# Xor_Not.net
KiCad netlist of a schematic drawn in EAGLE
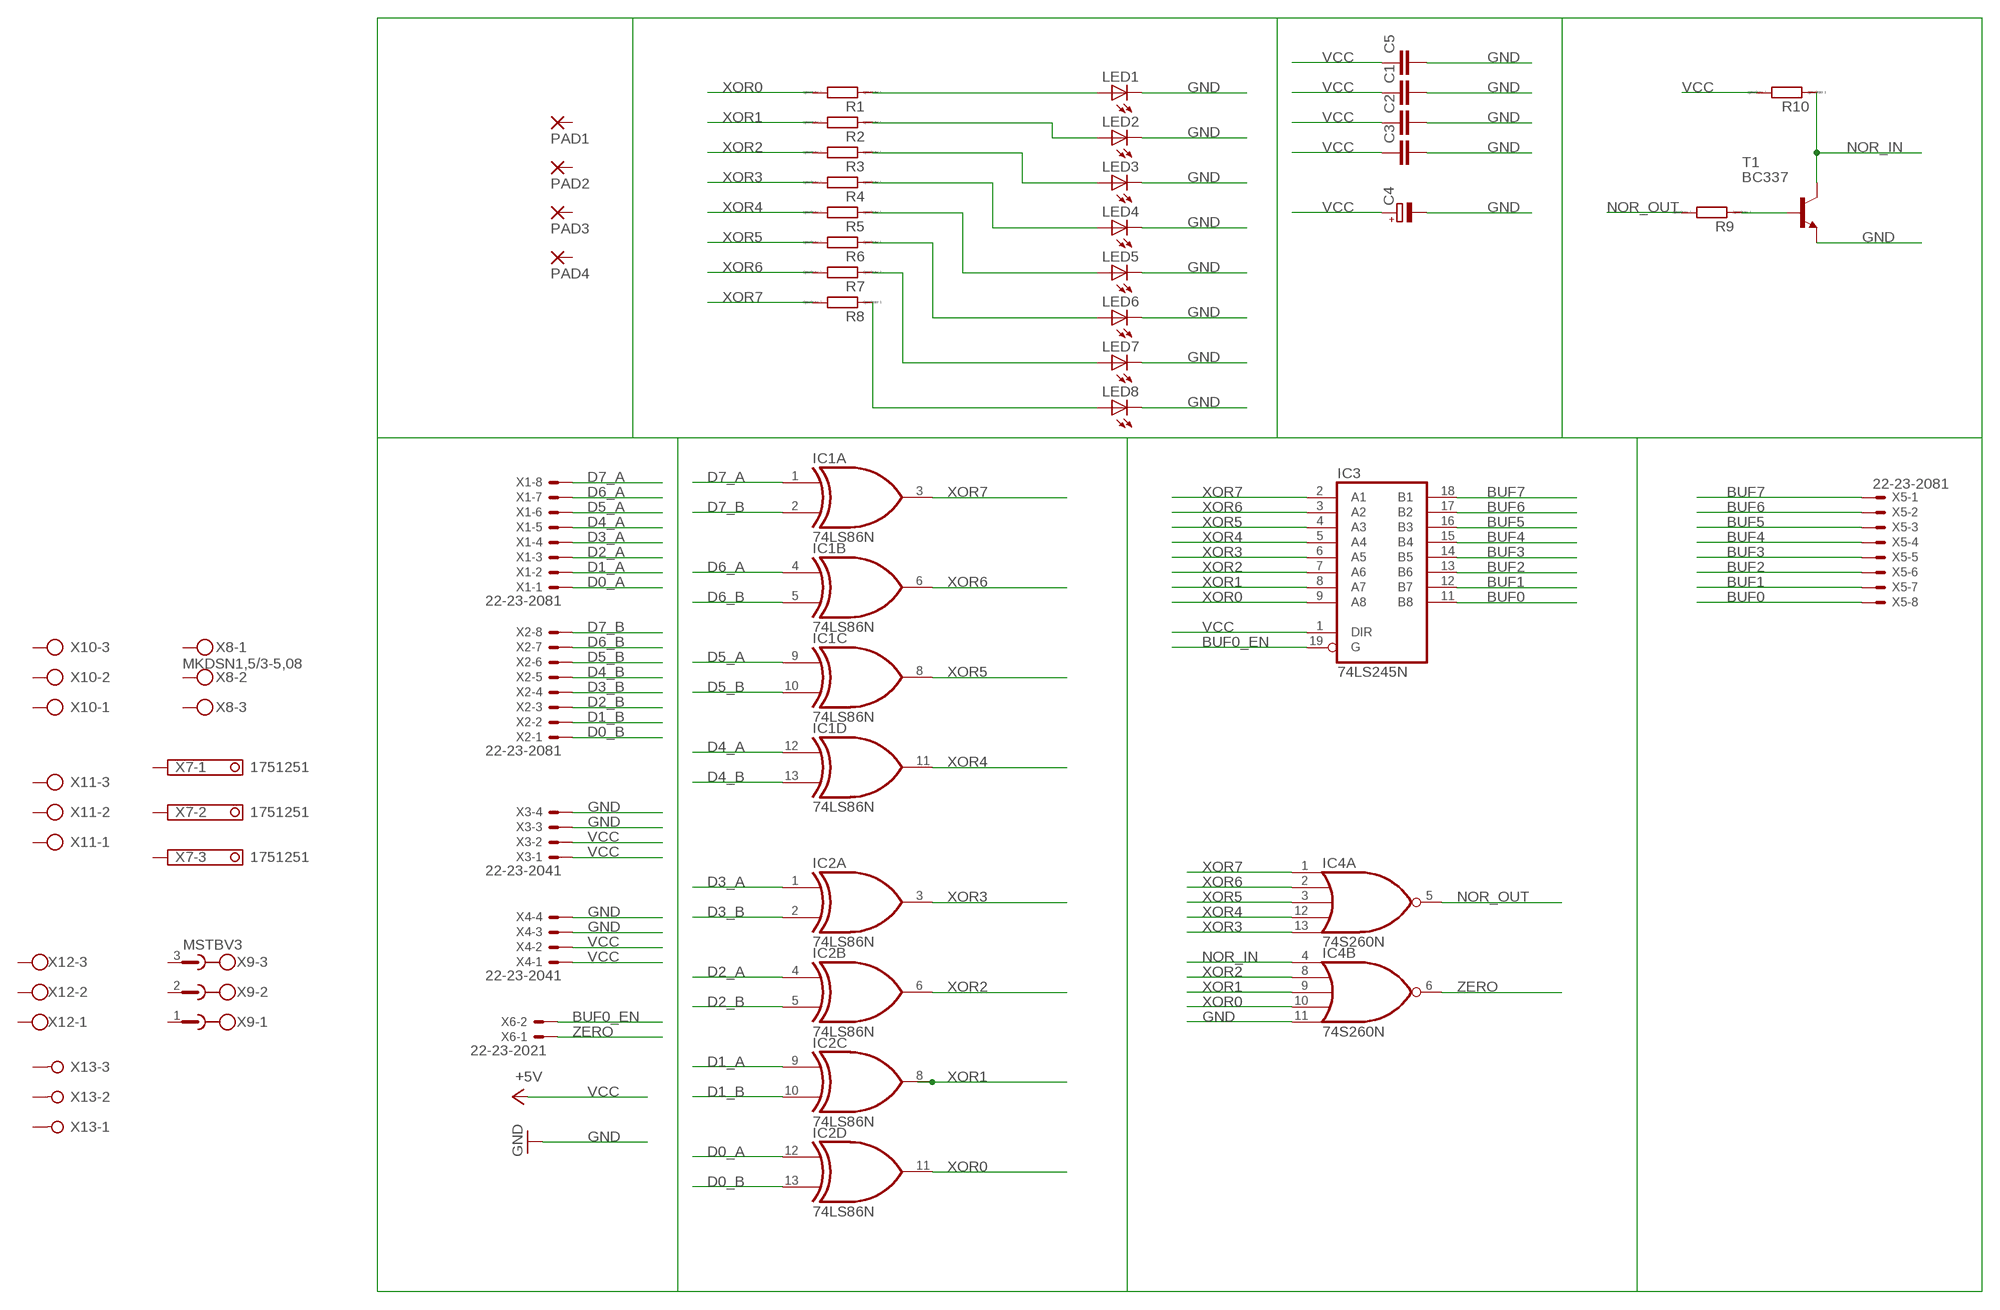
[diagram p0: schematic, sheet 1]

(export (version "E")
  (design (tool "Eeschema 10.0.6"))
  (components
    (comp (ref "C1")
      (value "C-EU025-025X050")
      (footprint "eagle-import:C025-025X050")
      (libsource (lib "eagle-import") (part "C-EU025-025X050"))
    )
    (comp (ref "C2")
      (value "C-EU025-025X050")
      (footprint "eagle-import:C025-025X050")
      (libsource (lib "eagle-import") (part "C-EU025-025X050"))
    )
    (comp (ref "C3")
      (value "C-EU025-025X050")
      (footprint "eagle-import:C025-025X050")
      (libsource (lib "eagle-import") (part "C-EU025-025X050"))
    )
    (comp (ref "C4")
      (value "CPOL-EUE2.5-6")
      (footprint "eagle-import:E2,5-6")
      (libsource (lib "eagle-import") (part "CPOL-EUE2.5-6"))
    )
    (comp (ref "C5")
      (value "C-EU025-025X050")
      (footprint "eagle-import:C025-025X050")
      (libsource (lib "eagle-import") (part "C-EU025-025X050"))
    )
    (comp (ref "IC1")
      (value "74LS86N")
      (footprint "eagle-import:DIL14")
      (libsource (lib "eagle-import") (part "7486NLS"))
    )
    (comp (ref "IC2")
      (value "74LS86N")
      (footprint "eagle-import:DIL14")
      (libsource (lib "eagle-import") (part "7486NLS"))
    )
    (comp (ref "IC3")
      (value "74LS245N")
      (footprint "eagle-import:DIL20")
      (libsource (lib "eagle-import") (part "74245NLS"))
    )
    (comp (ref "IC4")
      (value "74S260N")
      (footprint "eagle-import:DIL14")
      (libsource (lib "eagle-import") (part "74260NS"))
    )
    (comp (ref "LED1")
      (value "LED5MM")
      (footprint "eagle-import:LED5MM")
      (libsource (lib "eagle-import") (part "LED5MM"))
    )
    (comp (ref "LED2")
      (value "LED5MM")
      (footprint "eagle-import:LED5MM")
      (libsource (lib "eagle-import") (part "LED5MM"))
    )
    (comp (ref "LED3")
      (value "LED5MM")
      (footprint "eagle-import:LED5MM")
      (libsource (lib "eagle-import") (part "LED5MM"))
    )
    (comp (ref "LED4")
      (value "LED5MM")
      (footprint "eagle-import:LED5MM")
      (libsource (lib "eagle-import") (part "LED5MM"))
    )
    (comp (ref "LED5")
      (value "LED5MM")
      (footprint "eagle-import:LED5MM")
      (libsource (lib "eagle-import") (part "LED5MM"))
    )
    (comp (ref "LED6")
      (value "LED5MM")
      (footprint "eagle-import:LED5MM")
      (libsource (lib "eagle-import") (part "LED5MM"))
    )
    (comp (ref "LED7")
      (value "LED5MM")
      (footprint "eagle-import:LED5MM")
      (libsource (lib "eagle-import") (part "LED5MM"))
    )
    (comp (ref "LED8")
      (value "LED5MM")
      (footprint "eagle-import:LED5MM")
      (libsource (lib "eagle-import") (part "LED5MM"))
    )
    (comp (ref "PAD1")
      (value "3,17/1,3")
      (footprint "eagle-import:3,17_1,3")
      (libsource (lib "eagle-import") (part "3,17/1,3"))
    )
    (comp (ref "PAD2")
      (value "3,17/1,3")
      (footprint "eagle-import:3,17_1,3")
      (libsource (lib "eagle-import") (part "3,17/1,3"))
    )
    (comp (ref "PAD3")
      (value "3,17/1,3")
      (footprint "eagle-import:3,17_1,3")
      (libsource (lib "eagle-import") (part "3,17/1,3"))
    )
    (comp (ref "PAD4")
      (value "3,17/1,3")
      (footprint "eagle-import:3,17_1,3")
      (libsource (lib "eagle-import") (part "3,17/1,3"))
    )
    (comp (ref "R1")
      (value "R0207/10")
      (footprint "eagle-import:0207_10")
      (libsource (lib "eagle-import") (part "R0207/10"))
    )
    (comp (ref "R2")
      (value "R0207/10")
      (footprint "eagle-import:0207_10")
      (libsource (lib "eagle-import") (part "R0207/10"))
    )
    (comp (ref "R3")
      (value "R0207/10")
      (footprint "eagle-import:0207_10")
      (libsource (lib "eagle-import") (part "R0207/10"))
    )
    (comp (ref "R4")
      (value "R0207/10")
      (footprint "eagle-import:0207_10")
      (libsource (lib "eagle-import") (part "R0207/10"))
    )
    (comp (ref "R5")
      (value "R0207/10")
      (footprint "eagle-import:0207_10")
      (libsource (lib "eagle-import") (part "R0207/10"))
    )
    (comp (ref "R6")
      (value "R0207/10")
      (footprint "eagle-import:0207_10")
      (libsource (lib "eagle-import") (part "R0207/10"))
    )
    (comp (ref "R7")
      (value "R0207/10")
      (footprint "eagle-import:0207_10")
      (libsource (lib "eagle-import") (part "R0207/10"))
    )
    (comp (ref "R8")
      (value "R0207/10")
      (footprint "eagle-import:0207_10")
      (libsource (lib "eagle-import") (part "R0207/10"))
    )
    (comp (ref "R9")
      (value "R0207/10")
      (footprint "eagle-import:0207_10")
      (libsource (lib "eagle-import") (part "R0207/10"))
    )
    (comp (ref "R10")
      (value "R0207/10")
      (footprint "eagle-import:0207_10")
      (libsource (lib "eagle-import") (part "R0207/10"))
    )
    (comp (ref "T1")
      (value "BC337")
      (footprint "eagle-import:TO92")
      (libsource (lib "eagle-import") (part "BC337"))
    )
    (comp (ref "X1")
      (value "22-23-2081")
      (footprint "eagle-import:22-23-2081")
      (fields (field (name "MF") "MOLEX"))
      (libsource (lib "eagle-import") (part "22-23-2081"))
    )
    (comp (ref "X2")
      (value "22-23-2081")
      (footprint "eagle-import:22-23-2081")
      (fields (field (name "MF") "MOLEX"))
      (libsource (lib "eagle-import") (part "22-23-2081"))
    )
    (comp (ref "X3")
      (value "22-23-2041")
      (footprint "eagle-import:22-23-2041")
      (fields (field (name "MF") "MOLEX"))
      (libsource (lib "eagle-import") (part "22-23-2041"))
    )
    (comp (ref "X4")
      (value "22-23-2041")
      (footprint "eagle-import:22-23-2041")
      (fields (field (name "MF") "MOLEX"))
      (libsource (lib "eagle-import") (part "22-23-2041"))
    )
    (comp (ref "X5")
      (value "22-23-2081")
      (footprint "eagle-import:22-23-2081")
      (fields (field (name "MF") "MOLEX"))
      (libsource (lib "eagle-import") (part "22-23-2081"))
    )
    (comp (ref "X6")
      (value "22-23-2021")
      (footprint "eagle-import:22-23-2021")
      (fields (field (name "MF") "MOLEX"))
      (libsource (lib "eagle-import") (part "22-23-2021"))
    )
    (comp (ref "X7")
      (value "1751251")
      (footprint "eagle-import:1751251")
      (libsource (lib "eagle-import") (part "1751251"))
    )
    (comp (ref "X8")
      (value "MKDSN1,5/3-5,08")
      (footprint "eagle-import:MKDSN1,5_3-5,08")
      (libsource (lib "eagle-import") (part "MKDSN1,5/3-5,08"))
    )
    (comp (ref "X9")
      (value "MSTBV3")
      (footprint "eagle-import:MSTBV3")
      (fields (field (name "MPN") "MSTBV 2,5/3-GF-5.08"))
      (libsource (lib "eagle-import") (part "MSTBV3"))
    )
    (comp (ref "X10")
      (value "AK300/3")
      (footprint "eagle-import:AK300_3")
      (libsource (lib "eagle-import") (part "AK300/3"))
    )
    (comp (ref "X11")
      (value "AK500/3-H")
      (footprint "eagle-import:AK500_3-H")
      (libsource (lib "eagle-import") (part "AK500/3-H"))
    )
    (comp (ref "X12")
      (value "W237-103")
      (footprint "eagle-import:W237-103")
      (fields (field (name "MPN") "237-103"))
      (libsource (lib "eagle-import") (part "W237-103"))
    )
    (comp (ref "X13")
      (value "W237-03P")
      (footprint "eagle-import:W237-133")
      (libsource (lib "eagle-import") (part "W237-03P"))
    )
  )
  (nets
    (net (code "1") (name "+5V") (class "Default")
      (node (ref "C1") (pin "1") (pinfunction "1_1") (pintype "passive"))
      (node (ref "C2") (pin "1") (pinfunction "1_1") (pintype "passive"))
      (node (ref "C3") (pin "1") (pinfunction "1_1") (pintype "passive"))
      (node (ref "C4") (pin "+") (pinfunction "+_+") (pintype "passive"))
      (node (ref "C5") (pin "1") (pinfunction "1_1") (pintype "passive"))
      (node (ref "IC3") (pin "1") (pinfunction "DIR_1") (pintype "input"))
      (node (ref "R10") (pin "2") (pinfunction "2_2") (pintype "passive"))
      (node (ref "X3") (pin "1") (pinfunction "S_1") (pintype "passive"))
      (node (ref "X3") (pin "2") (pinfunction "S_2") (pintype "passive"))
      (node (ref "X4") (pin "1") (pinfunction "S_1") (pintype "passive"))
      (node (ref "X4") (pin "2") (pinfunction "S_2") (pintype "passive"))
    )
    (net (code "2") (name "/BUF0") (class "Default")
      (node (ref "IC3") (pin "11") (pinfunction "B8_11") (pintype "bidirectional"))
      (node (ref "X5") (pin "8") (pinfunction "S_8") (pintype "passive"))
    )
    (net (code "3") (name "/BUF0_EN") (class "Default")
      (node (ref "IC3") (pin "19") (pinfunction "G_19") (pintype "input"))
      (node (ref "X6") (pin "2") (pinfunction "S_2") (pintype "passive"))
    )
    (net (code "4") (name "/BUF1") (class "Default")
      (node (ref "IC3") (pin "12") (pinfunction "B7_12") (pintype "bidirectional"))
      (node (ref "X5") (pin "7") (pinfunction "S_7") (pintype "passive"))
    )
    (net (code "5") (name "/BUF2") (class "Default")
      (node (ref "IC3") (pin "13") (pinfunction "B6_13") (pintype "bidirectional"))
      (node (ref "X5") (pin "6") (pinfunction "S_6") (pintype "passive"))
    )
    (net (code "6") (name "/BUF3") (class "Default")
      (node (ref "IC3") (pin "14") (pinfunction "B5_14") (pintype "bidirectional"))
      (node (ref "X5") (pin "5") (pinfunction "S_5") (pintype "passive"))
    )
    (net (code "7") (name "/BUF4") (class "Default")
      (node (ref "IC3") (pin "15") (pinfunction "B4_15") (pintype "bidirectional"))
      (node (ref "X5") (pin "4") (pinfunction "S_4") (pintype "passive"))
    )
    (net (code "8") (name "/BUF5") (class "Default")
      (node (ref "IC3") (pin "16") (pinfunction "B3_16") (pintype "bidirectional"))
      (node (ref "X5") (pin "3") (pinfunction "S_3") (pintype "passive"))
    )
    (net (code "9") (name "/BUF6") (class "Default")
      (node (ref "IC3") (pin "17") (pinfunction "B2_17") (pintype "bidirectional"))
      (node (ref "X5") (pin "2") (pinfunction "S_2") (pintype "passive"))
    )
    (net (code "10") (name "/BUF7") (class "Default")
      (node (ref "IC3") (pin "18") (pinfunction "B1_18") (pintype "bidirectional"))
      (node (ref "X5") (pin "1") (pinfunction "S_1") (pintype "passive"))
    )
    (net (code "11") (name "/D0_A") (class "Default")
      (node (ref "IC2") (pin "12") (pinfunction "I0_12") (pintype "input"))
      (node (ref "X1") (pin "1") (pinfunction "S_1") (pintype "passive"))
    )
    (net (code "12") (name "/D0_B") (class "Default")
      (node (ref "IC2") (pin "13") (pinfunction "I1_13") (pintype "input"))
      (node (ref "X2") (pin "1") (pinfunction "S_1") (pintype "passive"))
    )
    (net (code "13") (name "/D1_A") (class "Default")
      (node (ref "IC2") (pin "9") (pinfunction "I0_9") (pintype "input"))
      (node (ref "X1") (pin "2") (pinfunction "S_2") (pintype "passive"))
    )
    (net (code "14") (name "/D1_B") (class "Default")
      (node (ref "IC2") (pin "10") (pinfunction "I1_10") (pintype "input"))
      (node (ref "X2") (pin "2") (pinfunction "S_2") (pintype "passive"))
    )
    (net (code "15") (name "/D2_A") (class "Default")
      (node (ref "IC2") (pin "4") (pinfunction "I0_4") (pintype "input"))
      (node (ref "X1") (pin "3") (pinfunction "S_3") (pintype "passive"))
    )
    (net (code "16") (name "/D2_B") (class "Default")
      (node (ref "IC2") (pin "5") (pinfunction "I1_5") (pintype "input"))
      (node (ref "X2") (pin "3") (pinfunction "S_3") (pintype "passive"))
    )
    (net (code "17") (name "/D3_A") (class "Default")
      (node (ref "IC2") (pin "1") (pinfunction "I0_1") (pintype "input"))
      (node (ref "X1") (pin "4") (pinfunction "S_4") (pintype "passive"))
    )
    (net (code "18") (name "/D3_B") (class "Default")
      (node (ref "IC2") (pin "2") (pinfunction "I1_2") (pintype "input"))
      (node (ref "X2") (pin "4") (pinfunction "S_4") (pintype "passive"))
    )
    (net (code "19") (name "/D4_A") (class "Default")
      (node (ref "IC1") (pin "12") (pinfunction "I0_12") (pintype "input"))
      (node (ref "X1") (pin "5") (pinfunction "S_5") (pintype "passive"))
    )
    (net (code "20") (name "/D4_B") (class "Default")
      (node (ref "IC1") (pin "13") (pinfunction "I1_13") (pintype "input"))
      (node (ref "X2") (pin "5") (pinfunction "S_5") (pintype "passive"))
    )
    (net (code "21") (name "/D5_A") (class "Default")
      (node (ref "IC1") (pin "9") (pinfunction "I0_9") (pintype "input"))
      (node (ref "X1") (pin "6") (pinfunction "S_6") (pintype "passive"))
    )
    (net (code "22") (name "/D5_B") (class "Default")
      (node (ref "IC1") (pin "10") (pinfunction "I1_10") (pintype "input"))
      (node (ref "X2") (pin "6") (pinfunction "S_6") (pintype "passive"))
    )
    (net (code "23") (name "/D6_A") (class "Default")
      (node (ref "IC1") (pin "4") (pinfunction "I0_4") (pintype "input"))
      (node (ref "X1") (pin "7") (pinfunction "S_7") (pintype "passive"))
    )
    (net (code "24") (name "/D6_B") (class "Default")
      (node (ref "IC1") (pin "5") (pinfunction "I1_5") (pintype "input"))
      (node (ref "X2") (pin "7") (pinfunction "S_7") (pintype "passive"))
    )
    (net (code "25") (name "/D7_A") (class "Default")
      (node (ref "IC1") (pin "1") (pinfunction "I0_1") (pintype "input"))
      (node (ref "X1") (pin "8") (pinfunction "S_8") (pintype "passive"))
    )
    (net (code "26") (name "/D7_B") (class "Default")
      (node (ref "IC1") (pin "2") (pinfunction "I1_2") (pintype "input"))
      (node (ref "X2") (pin "8") (pinfunction "S_8") (pintype "passive"))
    )
    (net (code "27") (name "/NOR_IN") (class "Default")
      (node (ref "IC4") (pin "4") (pinfunction "I0_4") (pintype "input"))
      (node (ref "R10") (pin "1") (pinfunction "1_1") (pintype "passive"))
      (node (ref "T1") (pin "3") (pinfunction "C_3") (pintype "passive"))
    )
    (net (code "28") (name "/NOR_OUT") (class "Default")
      (node (ref "IC4") (pin "5") (pinfunction "O_5") (pintype "output"))
      (node (ref "R9") (pin "2") (pinfunction "2_2") (pintype "passive"))
    )
    (net (code "29") (name "/XOR0") (class "Default")
      (node (ref "IC2") (pin "11") (pinfunction "O_11") (pintype "output"))
      (node (ref "IC3") (pin "9") (pinfunction "A8_9") (pintype "bidirectional"))
      (node (ref "IC4") (pin "10") (pinfunction "I3_10") (pintype "input"))
      (node (ref "R1") (pin "2") (pinfunction "2_2") (pintype "passive"))
    )
    (net (code "30") (name "/XOR1") (class "Default")
      (node (ref "IC2") (pin "8") (pinfunction "O_8") (pintype "output"))
      (node (ref "IC3") (pin "8") (pinfunction "A7_8") (pintype "bidirectional"))
      (node (ref "IC4") (pin "9") (pinfunction "I2_9") (pintype "input"))
      (node (ref "R2") (pin "2") (pinfunction "2_2") (pintype "passive"))
    )
    (net (code "31") (name "/XOR2") (class "Default")
      (node (ref "IC2") (pin "6") (pinfunction "O_6") (pintype "output"))
      (node (ref "IC3") (pin "7") (pinfunction "A6_7") (pintype "bidirectional"))
      (node (ref "IC4") (pin "8") (pinfunction "I1_8") (pintype "input"))
      (node (ref "R3") (pin "2") (pinfunction "2_2") (pintype "passive"))
    )
    (net (code "32") (name "/XOR3") (class "Default")
      (node (ref "IC2") (pin "3") (pinfunction "O_3") (pintype "output"))
      (node (ref "IC3") (pin "6") (pinfunction "A5_6") (pintype "bidirectional"))
      (node (ref "IC4") (pin "13") (pinfunction "I4_13") (pintype "input"))
      (node (ref "R4") (pin "2") (pinfunction "2_2") (pintype "passive"))
    )
    (net (code "33") (name "/XOR4") (class "Default")
      (node (ref "IC1") (pin "11") (pinfunction "O_11") (pintype "output"))
      (node (ref "IC3") (pin "5") (pinfunction "A4_5") (pintype "bidirectional"))
      (node (ref "IC4") (pin "12") (pinfunction "I3_12") (pintype "input"))
      (node (ref "R5") (pin "2") (pinfunction "2_2") (pintype "passive"))
    )
    (net (code "34") (name "/XOR5") (class "Default")
      (node (ref "IC1") (pin "8") (pinfunction "O_8") (pintype "output"))
      (node (ref "IC3") (pin "4") (pinfunction "A3_4") (pintype "bidirectional"))
      (node (ref "IC4") (pin "3") (pinfunction "I2_3") (pintype "input"))
      (node (ref "R6") (pin "2") (pinfunction "2_2") (pintype "passive"))
    )
    (net (code "35") (name "/XOR6") (class "Default")
      (node (ref "IC1") (pin "6") (pinfunction "O_6") (pintype "output"))
      (node (ref "IC3") (pin "3") (pinfunction "A2_3") (pintype "bidirectional"))
      (node (ref "IC4") (pin "2") (pinfunction "I1_2") (pintype "input"))
      (node (ref "R7") (pin "2") (pinfunction "2_2") (pintype "passive"))
    )
    (net (code "36") (name "/XOR7") (class "Default")
      (node (ref "IC1") (pin "3") (pinfunction "O_3") (pintype "output"))
      (node (ref "IC3") (pin "2") (pinfunction "A1_2") (pintype "bidirectional"))
      (node (ref "IC4") (pin "1") (pinfunction "I0_1") (pintype "input"))
      (node (ref "R8") (pin "2") (pinfunction "2_2") (pintype "passive"))
    )
    (net (code "37") (name "/ZERO") (class "Default")
      (node (ref "IC4") (pin "6") (pinfunction "O_6") (pintype "output"))
      (node (ref "X6") (pin "1") (pinfunction "S_1") (pintype "passive"))
    )
    (net (code "38") (name "GND") (class "Default")
      (node (ref "C1") (pin "2") (pinfunction "2_2") (pintype "passive"))
      (node (ref "C2") (pin "2") (pinfunction "2_2") (pintype "passive"))
      (node (ref "C3") (pin "2") (pinfunction "2_2") (pintype "passive"))
      (node (ref "C4") (pin "-") (pinfunction "-_-") (pintype "passive"))
      (node (ref "C5") (pin "2") (pinfunction "2_2") (pintype "passive"))
      (node (ref "IC4") (pin "11") (pinfunction "I4_11") (pintype "input"))
      (node (ref "LED1") (pin "K") (pinfunction "C_K") (pintype "passive"))
      (node (ref "LED2") (pin "K") (pinfunction "C_K") (pintype "passive"))
      (node (ref "LED3") (pin "K") (pinfunction "C_K") (pintype "passive"))
      (node (ref "LED4") (pin "K") (pinfunction "C_K") (pintype "passive"))
      (node (ref "LED5") (pin "K") (pinfunction "C_K") (pintype "passive"))
      (node (ref "LED6") (pin "K") (pinfunction "C_K") (pintype "passive"))
      (node (ref "LED7") (pin "K") (pinfunction "C_K") (pintype "passive"))
      (node (ref "LED8") (pin "K") (pinfunction "C_K") (pintype "passive"))
      (node (ref "T1") (pin "1") (pinfunction "E_1") (pintype "passive"))
      (node (ref "X3") (pin "3") (pinfunction "S_3") (pintype "passive"))
      (node (ref "X3") (pin "4") (pinfunction "S_4") (pintype "passive"))
      (node (ref "X4") (pin "3") (pinfunction "S_3") (pintype "passive"))
      (node (ref "X4") (pin "4") (pinfunction "S_4") (pintype "passive"))
    )
    (net (code "39") (name "Net-(LED1-PadA)") (class "Default")
      (node (ref "LED1") (pin "A") (pinfunction "A_A") (pintype "passive"))
      (node (ref "R1") (pin "1") (pinfunction "1_1") (pintype "passive"))
    )
    (net (code "40") (name "Net-(LED2-PadA)") (class "Default")
      (node (ref "LED2") (pin "A") (pinfunction "A_A") (pintype "passive"))
      (node (ref "R2") (pin "1") (pinfunction "1_1") (pintype "passive"))
    )
    (net (code "41") (name "Net-(LED3-PadA)") (class "Default")
      (node (ref "LED3") (pin "A") (pinfunction "A_A") (pintype "passive"))
      (node (ref "R3") (pin "1") (pinfunction "1_1") (pintype "passive"))
    )
    (net (code "42") (name "Net-(LED4-PadA)") (class "Default")
      (node (ref "LED4") (pin "A") (pinfunction "A_A") (pintype "passive"))
      (node (ref "R4") (pin "1") (pinfunction "1_1") (pintype "passive"))
    )
    (net (code "43") (name "Net-(LED5-PadA)") (class "Default")
      (node (ref "LED5") (pin "A") (pinfunction "A_A") (pintype "passive"))
      (node (ref "R5") (pin "1") (pinfunction "1_1") (pintype "passive"))
    )
    (net (code "44") (name "Net-(LED6-PadA)") (class "Default")
      (node (ref "LED6") (pin "A") (pinfunction "A_A") (pintype "passive"))
      (node (ref "R6") (pin "1") (pinfunction "1_1") (pintype "passive"))
    )
    (net (code "45") (name "Net-(LED7-PadA)") (class "Default")
      (node (ref "LED7") (pin "A") (pinfunction "A_A") (pintype "passive"))
      (node (ref "R7") (pin "1") (pinfunction "1_1") (pintype "passive"))
    )
    (net (code "46") (name "Net-(LED8-PadA)") (class "Default")
      (node (ref "LED8") (pin "A") (pinfunction "A_A") (pintype "passive"))
      (node (ref "R8") (pin "1") (pinfunction "1_1") (pintype "passive"))
    )
    (net (code "47") (name "Net-(T1-B)") (class "Default")
      (node (ref "R9") (pin "1") (pinfunction "1_1") (pintype "passive"))
      (node (ref "T1") (pin "2") (pinfunction "B_2") (pintype "passive"))
    )
    (net (code "48") (name "unconnected-(PAD1-P-Pad1)") (class "Default")
      (node (ref "PAD1") (pin "1") (pinfunction "P_1") (pintype "passive"))
    )
    (net (code "49") (name "unconnected-(PAD2-P-Pad1)") (class "Default")
      (node (ref "PAD2") (pin "1") (pinfunction "P_1") (pintype "passive"))
    )
    (net (code "50") (name "unconnected-(PAD3-P-Pad1)") (class "Default")
      (node (ref "PAD3") (pin "1") (pinfunction "P_1") (pintype "passive"))
    )
    (net (code "51") (name "unconnected-(PAD4-P-Pad1)") (class "Default")
      (node (ref "PAD4") (pin "1") (pinfunction "P_1") (pintype "passive"))
    )
    (net (code "52") (name "unconnected-(X7A-K-Pad1)") (class "Default")
      (node (ref "X7") (pin "1") (pinfunction "K_1") (pintype "passive"))
    )
    (net (code "53") (name "unconnected-(X7B-K-Pad2)") (class "Default")
      (node (ref "X7") (pin "2") (pinfunction "K_2") (pintype "passive"))
    )
    (net (code "54") (name "unconnected-(X7C-K-Pad3)") (class "Default")
      (node (ref "X7") (pin "3") (pinfunction "K_3") (pintype "passive"))
    )
    (net (code "55") (name "unconnected-(X8A-KL-Pad1)") (class "Default")
      (node (ref "X8") (pin "1") (pinfunction "KL_1") (pintype "passive"))
    )
    (net (code "56") (name "unconnected-(X8B-KL-Pad2)") (class "Default")
      (node (ref "X8") (pin "2") (pinfunction "KL_2") (pintype "passive"))
    )
    (net (code "57") (name "unconnected-(X8C-KL-Pad3)") (class "Default")
      (node (ref "X8") (pin "3") (pinfunction "KL_3") (pintype "passive"))
    )
    (net (code "58") (name "unconnected-(X9-Pad1)") (class "Default")
      (node (ref "X9") (pin "1") (pinfunction "1_1") (pintype "passive"))
    )
    (net (code "59") (name "unconnected-(X9B-1-Pad2)") (class "Default")
      (node (ref "X9") (pin "2") (pinfunction "1_2") (pintype "passive"))
    )
    (net (code "60") (name "unconnected-(X9C-1-Pad3)") (class "Default")
      (node (ref "X9") (pin "3") (pinfunction "1_3") (pintype "passive"))
    )
    (net (code "61") (name "unconnected-(X10A-KL-Pad1)") (class "Default")
      (node (ref "X10") (pin "1") (pinfunction "KL_1") (pintype "passive"))
    )
    (net (code "62") (name "unconnected-(X10B-KL-Pad2)") (class "Default")
      (node (ref "X10") (pin "2") (pinfunction "KL_2") (pintype "passive"))
    )
    (net (code "63") (name "unconnected-(X10C-KL-Pad3)") (class "Default")
      (node (ref "X10") (pin "3") (pinfunction "KL_3") (pintype "passive"))
    )
    (net (code "64") (name "unconnected-(X11A-KL-Pad1)") (class "Default")
      (node (ref "X11") (pin "1") (pinfunction "KL_1") (pintype "passive"))
    )
    (net (code "65") (name "unconnected-(X11B-KL-Pad2)") (class "Default")
      (node (ref "X11") (pin "2") (pinfunction "KL_2") (pintype "passive"))
    )
    (net (code "66") (name "unconnected-(X11C-KL-Pad3)") (class "Default")
      (node (ref "X11") (pin "3") (pinfunction "KL_3") (pintype "passive"))
    )
    (net (code "67") (name "unconnected-(X12A-KL-Pad1)") (class "Default")
      (node (ref "X12") (pin "1") (pinfunction "KL_1") (pintype "passive"))
    )
    (net (code "68") (name "unconnected-(X12B-KL-Pad2)") (class "Default")
      (node (ref "X12") (pin "2") (pinfunction "KL_2") (pintype "passive"))
    )
    (net (code "69") (name "unconnected-(X12C-KL-Pad3)") (class "Default")
      (node (ref "X12") (pin "3") (pinfunction "KL_3") (pintype "passive"))
    )
    (net (code "70") (name "unconnected-(X13A-KL-Pad1)") (class "Default")
      (node (ref "X13") (pin "1") (pinfunction "KL_1") (pintype "passive"))
    )
    (net (code "71") (name "unconnected-(X13B-KL-Pad2)") (class "Default")
      (node (ref "X13") (pin "2") (pinfunction "KL_2") (pintype "passive"))
    )
    (net (code "72") (name "unconnected-(X13C-KL-Pad3)") (class "Default")
      (node (ref "X13") (pin "3") (pinfunction "KL_3") (pintype "passive"))
    )
  )
)
